# Half-Bridge.net
KiCad netlist of a schematic drawn in Altium Designer
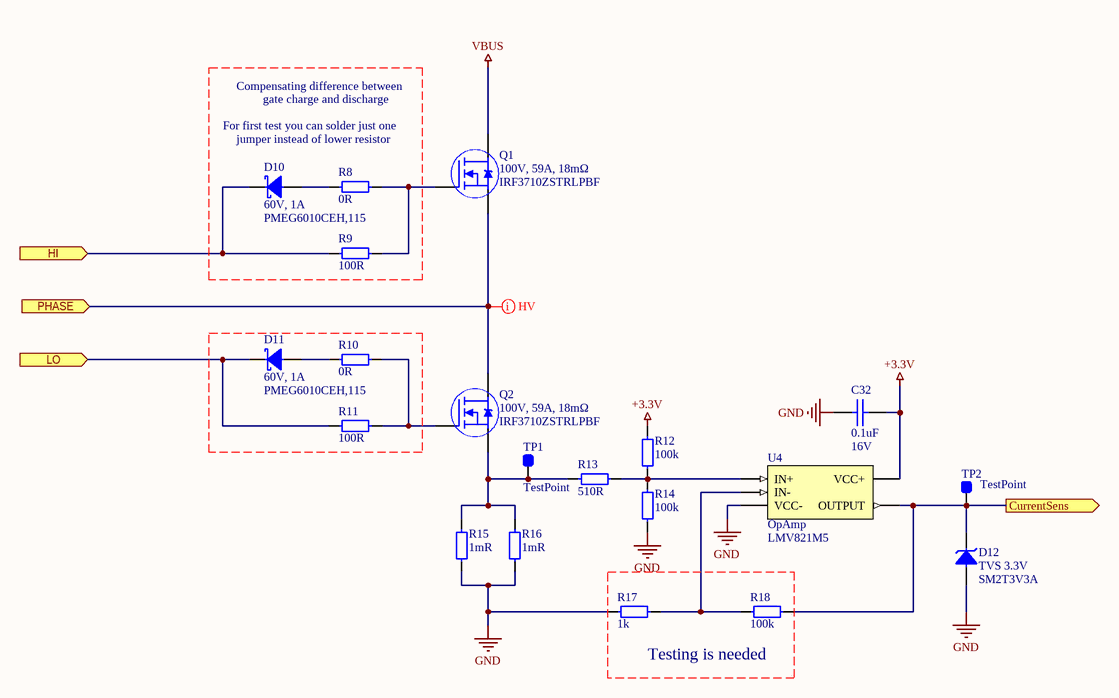
[diagram p0: Half-Bridge.SchDoc]

(export (version "E")
  (design (tool "Eeschema 10.0.6"))
  (components
    (comp (ref "C32")
      (value "0.1uF")
      (footprint "0603 Capicator")
      (description "0.1uF X7R 16V 10% 0603")
      (fields
        (field (name "MANUFACTURER") "Murata Manufacturing")
        (field (name "PART NUMBER") "GRM188R71C104KA01D")
        (field (name "VOLTAGE") "16V")
      )
      (libsource (lib "Karen_Components") (part "Cap 0.1uF (0603)"))
    )
    (comp (ref "D10")
      (value "60V, 1A")
      (footprint "SOD-123FL")
      (fields (field (name "MANUFACTURER") "Nexperia") (field (name "PART NUMBER") "PMEG6010CEH,115"))
      (libsource (lib "Karen_Components") (part "Diode Schottky 60V (SOD-123FL)"))
    )
    (comp (ref "D11")
      (value "60V, 1A")
      (footprint "SOD-123FL")
      (fields (field (name "MANUFACTURER") "Nexperia") (field (name "PART NUMBER") "PMEG6010CEH,115"))
      (libsource (lib "Karen_Components") (part "Diode Schottky 60V (SOD-123FL)"))
    )
    (comp (ref "D12")
      (value "TVS 3.3V")
      (footprint "DO-216AA")
      (description "High peak pulse power: 200 W (10/1000 μs)")
      (fields (field (name "MANUFACTURER") "STMicroelectronics") (field (name "PART NUMBER") "SM2T3V3A"))
      (libsource (lib "Karen_Components") (part "TVS Diode 3.3V [SM2T]"))
    )
    (comp (ref "Q1")
      (value "100V, 59A, 18mΩ")
      (footprint "D2-PAK (TO-262)")
      (fields (field (name "MANUFACTURER") "Infineon") (field (name "PART NUMBER") "IRF3710ZSTRLPBF"))
      (libsource (lib "Karen_Components") (part "MOSFET-N [IRF]"))
    )
    (comp (ref "Q2")
      (value "100V, 59A, 18mΩ")
      (footprint "D2-PAK (TO-262)")
      (fields (field (name "MANUFACTURER") "Infineon") (field (name "PART NUMBER") "IRF3710ZSTRLPBF"))
      (libsource (lib "Karen_Components") (part "MOSFET-N [IRF]"))
    )
    (comp (ref "R8")
      (value "0R")
      (footprint "0603 Resistor")
      (description "0.1W 0603 0R, 5%")
      (fields (field (name "PART NUMBER") "RC0603JR-070RL") (field (name "MANUFACTURER") "Taiwan"))
      (libsource (lib "Karen_Components") (part "Res 0R (0603)"))
    )
    (comp (ref "R9")
      (value "100R")
      (footprint "0603 Resistor")
      (description "0.1W 0603 100R, 1%")
      (fields (field (name "PART NUMBER") "RC0603FR-07100RL") (field (name "MANUFACTURER") "Taiwan"))
      (libsource (lib "Karen_Components") (part "Res 100R (0603)"))
    )
    (comp (ref "R10")
      (value "0R")
      (footprint "0603 Resistor")
      (description "0.1W 0603 0R, 5%")
      (fields (field (name "PART NUMBER") "RC0603JR-070RL") (field (name "MANUFACTURER") "Taiwan"))
      (libsource (lib "Karen_Components") (part "Res 0R (0603)"))
    )
    (comp (ref "R11")
      (value "100R")
      (footprint "0603 Resistor")
      (description "0.1W 0603 100R, 1%")
      (fields (field (name "PART NUMBER") "RC0603FR-07100RL") (field (name "MANUFACTURER") "Taiwan"))
      (libsource (lib "Karen_Components") (part "Res 100R (0603)"))
    )
    (comp (ref "R12")
      (value "100k")
      (footprint "0603 Resistor")
      (description "0.1W 0603 100k, 1%")
      (fields (field (name "PART NUMBER") "RC0603FR-07100KL") (field (name "MANUFACTURER") "Taiwan"))
      (libsource (lib "Karen_Components") (part "Res 100k (0603)"))
    )
    (comp (ref "R13")
      (value "510R")
      (footprint "0603 Resistor")
      (description "0.1W 0603 510R, 1%")
      (fields (field (name "PART NUMBER") "RC0603FR-07510RL") (field (name "MANUFACTURER") "Taiwan"))
      (libsource (lib "Karen_Components") (part "Res 510R (0603)"))
    )
    (comp (ref "R14")
      (value "100k")
      (footprint "0603 Resistor")
      (description "0.1W 0603 100k, 1%")
      (fields (field (name "PART NUMBER") "RC0603FR-07100KL") (field (name "MANUFACTURER") "Taiwan"))
      (libsource (lib "Karen_Components") (part "Res 100k (0603)"))
    )
    (comp (ref "R15")
      (value "1mR")
      (footprint "2512 Resistor")
      (description "Current Shunt, 1W 2512 1mR 1%")
      (fields (field (name "PART NUMBER") "WSL25121L000FEA") (field (name "MANUFACTURER") "Vishay"))
      (libsource (lib "Karen_Components") (part "Res Precise 1mR (2512)"))
    )
    (comp (ref "R16")
      (value "1mR")
      (footprint "2512 Resistor")
      (description "Current Shunt, 1W 2512 1mR 1%")
      (fields (field (name "PART NUMBER") "WSL25121L000FEA") (field (name "MANUFACTURER") "Vishay"))
      (libsource (lib "Karen_Components") (part "Res Precise 1mR (2512)"))
    )
    (comp (ref "R17")
      (value "1k")
      (footprint "0603 Resistor")
      (description "0.1W 0603 1k, 1%")
      (fields (field (name "PART NUMBER") "RC0603FR-071KL") (field (name "MANUFACTURER") "Taiwan"))
      (libsource (lib "Karen_Components") (part "Res 1k (0603)"))
    )
    (comp (ref "R18")
      (value "100k")
      (footprint "0603 Resistor")
      (description "0.1W 0603 100k, 1%")
      (fields (field (name "PART NUMBER") "RC0603FR-07100KL") (field (name "MANUFACTURER") "Taiwan"))
      (libsource (lib "Karen_Components") (part "Res 100k (0603)"))
    )
    (comp (ref "TP1")
      (value "TestPoint")
      (footprint "TestPoint")
      (libsource (lib "Karen_Components") (part "TestPoint"))
    )
    (comp (ref "TP2")
      (value "TestPoint")
      (footprint "TestPoint")
      (libsource (lib "Karen_Components") (part "TestPoint"))
    )
    (comp (ref "U4")
      (value "OpAmp")
      (footprint "SOT-23-5")
      (fields (field (name "MANUFACTURER") "Texas Instruments") (field (name "PART NUMBER") "LMV821M5"))
      (libsource (lib "Karen_Components") (part "OpAmp [LMV821]"))
    )
  )
  (nets
    (net (code "1") (name "+3.3V") (class "Default")
      (node (ref "C32") (pin "1") (pinfunction "1_1") (pintype "passive"))
      (node (ref "R12") (pin "2") (pinfunction "2_2") (pintype "passive"))
      (node (ref "U4") (pin "5") (pinfunction "VCC+_5") (pintype "power_in"))
    )
    (net (code "2") (name "/CurrentSens") (class "Default")
      (node (ref "D12") (pin "2") (pinfunction "2_2") (pintype "passive"))
      (node (ref "R18") (pin "2") (pinfunction "2_2") (pintype "passive"))
      (node (ref "TP2") (pin "1") (pinfunction "1_1") (pintype "passive"))
      (node (ref "U4") (pin "4") (pinfunction "OUTPUT_4") (pintype "output"))
    )
    (net (code "3") (name "/HI") (class "Default")
      (node (ref "D10") (pin "2") (pinfunction "2_2") (pintype "passive"))
      (node (ref "R9") (pin "1") (pinfunction "1_1") (pintype "passive"))
    )
    (net (code "4") (name "/LO") (class "Default")
      (node (ref "D11") (pin "2") (pinfunction "2_2") (pintype "passive"))
      (node (ref "R11") (pin "1") (pinfunction "1_1") (pintype "passive"))
    )
    (net (code "5") (name "/PHASE") (class "Default")
      (node (ref "Q1") (pin "3") (pinfunction "Source_3") (pintype "passive"))
      (node (ref "Q2") (pin "2") (pinfunction "Drain_2") (pintype "passive"))
    )
    (net (code "6") (name "GND") (class "Default")
      (node (ref "C32") (pin "2") (pinfunction "2_2") (pintype "passive"))
      (node (ref "D12") (pin "1") (pinfunction "1_1") (pintype "passive"))
      (node (ref "R14") (pin "1") (pinfunction "1_1") (pintype "passive"))
      (node (ref "R15") (pin "1") (pinfunction "1_1") (pintype "passive"))
      (node (ref "R16") (pin "1") (pinfunction "1_1") (pintype "passive"))
      (node (ref "R17") (pin "1") (pinfunction "1_1") (pintype "passive"))
      (node (ref "U4") (pin "2") (pinfunction "VCC-_2") (pintype "power_in"))
    )
    (net (code "7") (name "Net-(D10-Pad1)") (class "Default")
      (node (ref "D10") (pin "1") (pinfunction "1_1") (pintype "passive"))
      (node (ref "R8") (pin "1") (pinfunction "1_1") (pintype "passive"))
    )
    (net (code "8") (name "Net-(D11-Pad1)") (class "Default")
      (node (ref "D11") (pin "1") (pinfunction "1_1") (pintype "passive"))
      (node (ref "R10") (pin "1") (pinfunction "1_1") (pintype "passive"))
    )
    (net (code "9") (name "Net-(Q1-Gate)") (class "Default")
      (node (ref "Q1") (pin "1") (pinfunction "Gate_1") (pintype "passive"))
      (node (ref "R8") (pin "2") (pinfunction "2_2") (pintype "passive"))
      (node (ref "R9") (pin "2") (pinfunction "2_2") (pintype "passive"))
    )
    (net (code "10") (name "Net-(Q2-Gate)") (class "Default")
      (node (ref "Q2") (pin "1") (pinfunction "Gate_1") (pintype "passive"))
      (node (ref "R10") (pin "2") (pinfunction "2_2") (pintype "passive"))
      (node (ref "R11") (pin "2") (pinfunction "2_2") (pintype "passive"))
    )
    (net (code "11") (name "Net-(Q2-Source)") (class "Default")
      (node (ref "Q2") (pin "3") (pinfunction "Source_3") (pintype "passive"))
      (node (ref "R13") (pin "1") (pinfunction "1_1") (pintype "passive"))
      (node (ref "R15") (pin "2") (pinfunction "2_2") (pintype "passive"))
      (node (ref "R16") (pin "2") (pinfunction "2_2") (pintype "passive"))
      (node (ref "TP1") (pin "1") (pinfunction "1_1") (pintype "passive"))
    )
    (net (code "12") (name "Net-(U4-IN+)") (class "Default")
      (node (ref "R12") (pin "1") (pinfunction "1_1") (pintype "passive"))
      (node (ref "R13") (pin "2") (pinfunction "2_2") (pintype "passive"))
      (node (ref "R14") (pin "2") (pinfunction "2_2") (pintype "passive"))
      (node (ref "U4") (pin "1") (pinfunction "IN+_1") (pintype "input"))
    )
    (net (code "13") (name "Net-(U4-IN-)") (class "Default")
      (node (ref "R17") (pin "2") (pinfunction "2_2") (pintype "passive"))
      (node (ref "R18") (pin "1") (pinfunction "1_1") (pintype "passive"))
      (node (ref "U4") (pin "3") (pinfunction "IN-_3") (pintype "input"))
    )
    (net (code "14") (name "VBUS") (class "Default")
      (node (ref "Q1") (pin "2") (pinfunction "Drain_2") (pintype "passive"))
    )
  )
)
